# adafruit_rgblcdplate.net
KiCad netlist of a schematic drawn in EAGLE
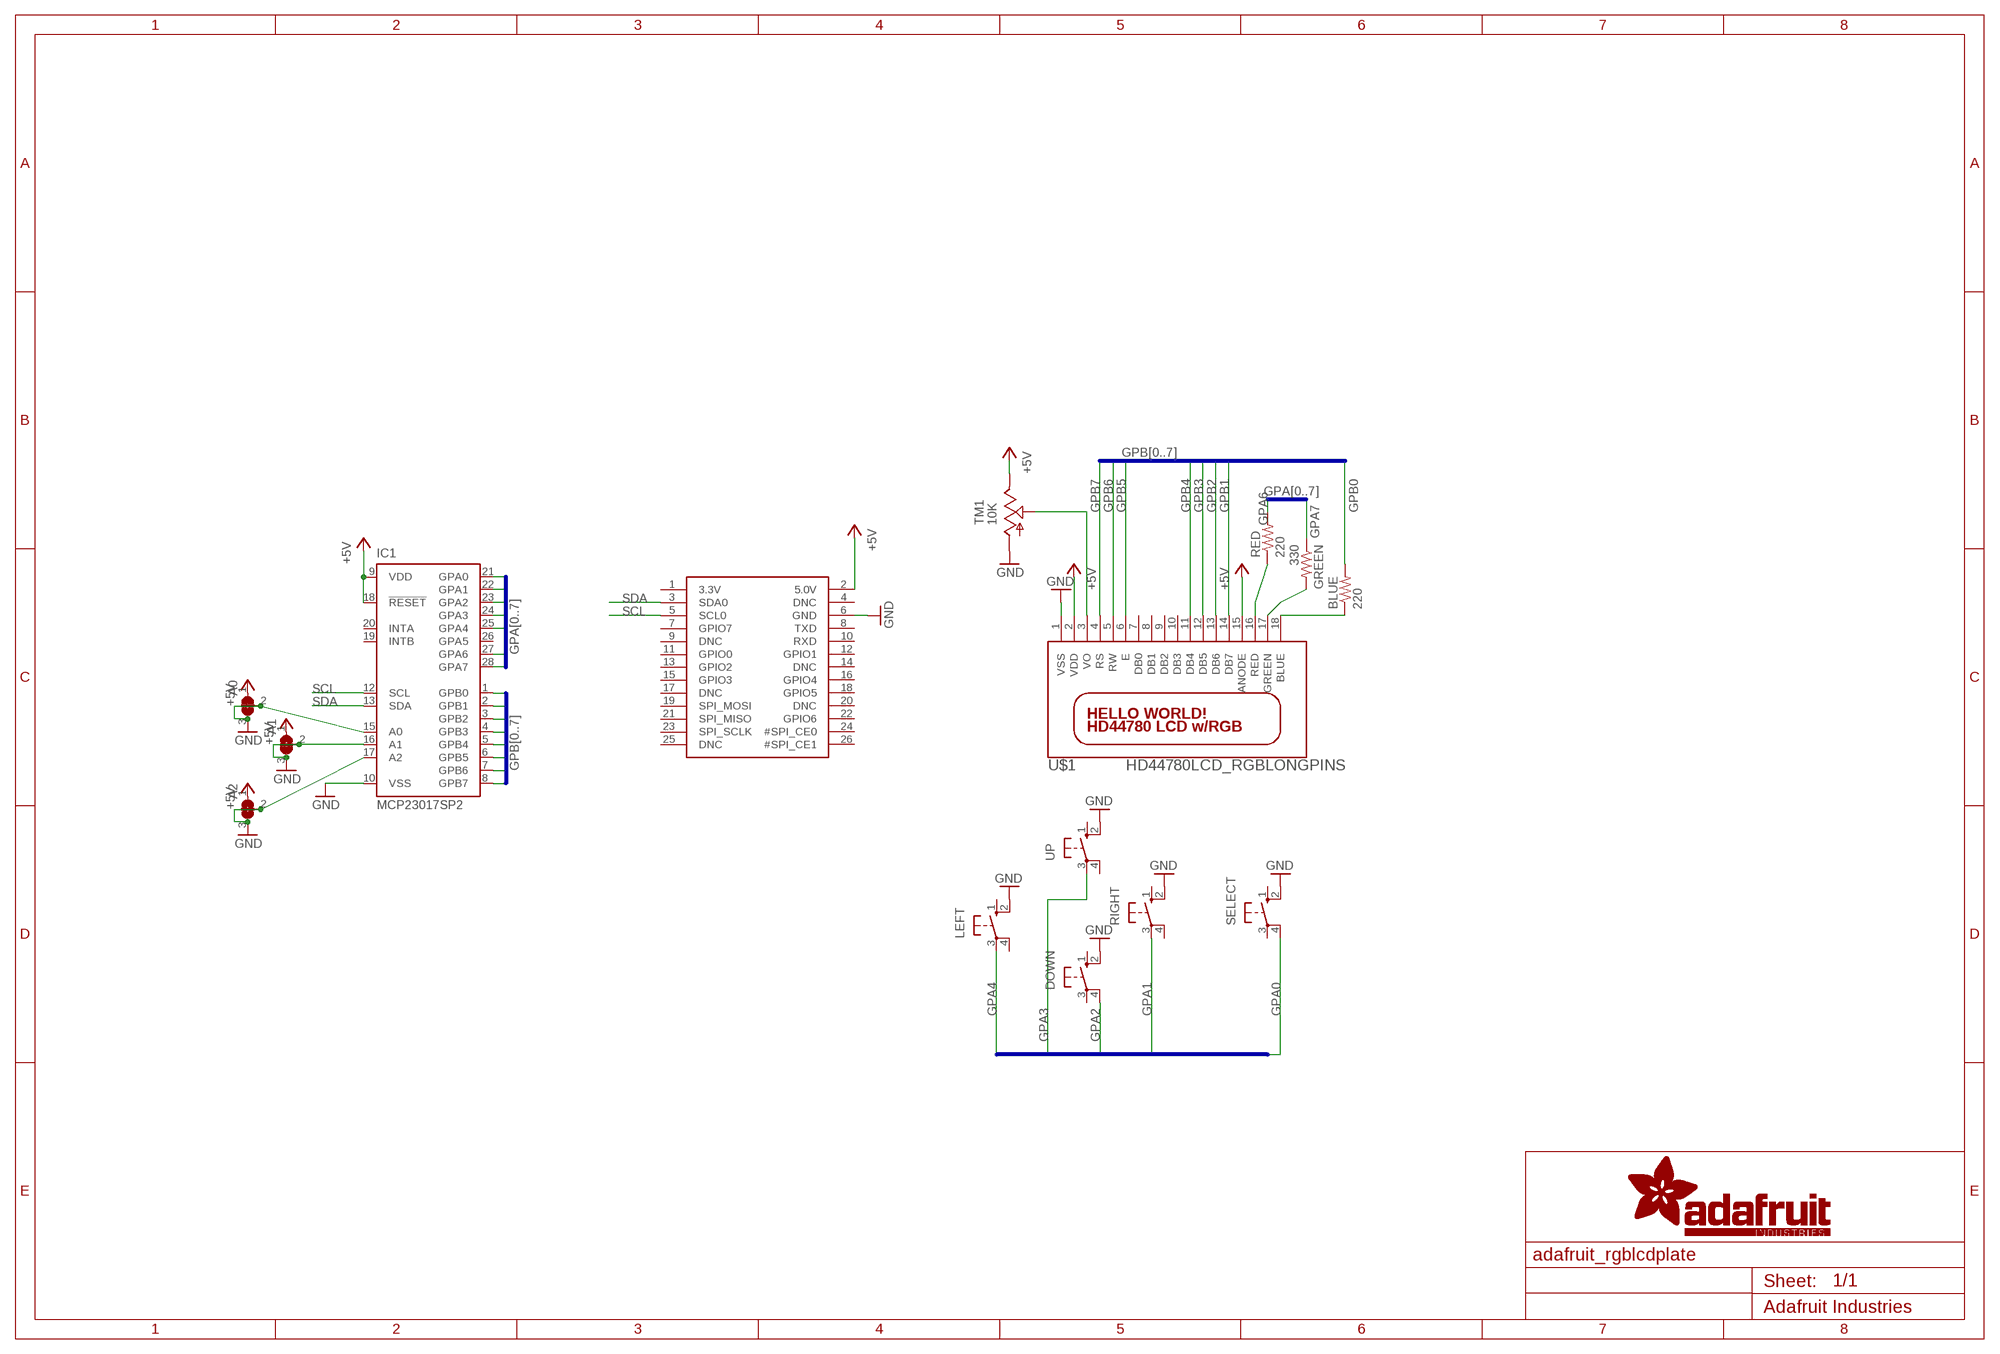
[diagram p0: schematic, sheet 1]

(export (version "E")
  (design (tool "Eeschema 10.0.6"))
  (components
    (comp (ref "A0")
      (value "SOLDERJUMPER_2WAY")
      (footprint "eagle-import:SOLDERJUMPER_2WAY_OPEN_NOPASTE")
      (libsource (lib "eagle-import") (part "SOLDERJUMPER_2WAY"))
    )
    (comp (ref "A1")
      (value "SOLDERJUMPER_2WAY")
      (footprint "eagle-import:SOLDERJUMPER_2WAY_OPEN_NOPASTE")
      (libsource (lib "eagle-import") (part "SOLDERJUMPER_2WAY"))
    )
    (comp (ref "A2")
      (value "SOLDERJUMPER_2WAY")
      (footprint "eagle-import:SOLDERJUMPER_2WAY_OPEN_NOPASTE")
      (libsource (lib "eagle-import") (part "SOLDERJUMPER_2WAY"))
    )
    (comp (ref "BLUE")
      (value "220")
      (footprint "eagle-import:0207_10")
      (libsource (lib "eagle-import") (part "R-US_0207/10"))
    )
    (comp (ref "DOWN")
      (value "10-XX")
      (footprint "eagle-import:B3F-10XX")
      (libsource (lib "eagle-import") (part "10-XX"))
    )
    (comp (ref "GREEN")
      (value "330")
      (footprint "eagle-import:0207_10")
      (libsource (lib "eagle-import") (part "R-US_0207/10"))
    )
    (comp (ref "IC1")
      (value "MCP23017SP2")
      (footprint "eagle-import:DIL28-3-ROUND")
      (libsource (lib "eagle-import") (part "MCP23017SP2"))
    )
    (comp (ref "LEFT")
      (value "10-XX")
      (footprint "eagle-import:B3F-10XX")
      (libsource (lib "eagle-import") (part "10-XX"))
    )
    (comp (ref "RED")
      (value "220")
      (footprint "eagle-import:0207_10")
      (libsource (lib "eagle-import") (part "R-US_0207/10"))
    )
    (comp (ref "RIGHT")
      (value "10-XX")
      (footprint "eagle-import:B3F-10XX")
      (libsource (lib "eagle-import") (part "10-XX"))
    )
    (comp (ref "SELECT")
      (value "10-XX")
      (footprint "eagle-import:B3F-10XX")
      (libsource (lib "eagle-import") (part "10-XX"))
    )
    (comp (ref "TM1")
      (value "10K")
      (footprint "eagle-import:6MM")
      (libsource (lib "eagle-import") (part "TRIM"))
    )
    (comp (ref "U$1")
      (value "HD44780LCD_RGBLONGPINS")
      (footprint "eagle-import:LCD1602-RGB")
      (libsource (lib "eagle-import") (part "HD44780LCD_RGBLONGPINS"))
    )
    (comp (ref "U$4")
      (value "RASPBERRYPI_BB")
      (footprint "eagle-import:RASBERRYPI_SHIELD")
      (libsource (lib "eagle-import") (part "RASPBERRYPI_BB"))
    )
    (comp (ref "UP")
      (value "10-XX")
      (footprint "eagle-import:B3F-10XX")
      (libsource (lib "eagle-import") (part "10-XX"))
    )
  )
  (nets
    (net (code "2") (name "+5V") (class "Default")
      (node (ref "A0") (pin "1") (pinfunction "1_1") (pintype "passive"))
      (node (ref "A1") (pin "1") (pinfunction "1_1") (pintype "passive"))
      (node (ref "A2") (pin "1") (pinfunction "1_1") (pintype "passive"))
      (node (ref "IC1") (pin "18") (pinfunction "~{RESET}_18") (pintype "input"))
      (node (ref "IC1") (pin "9") (pinfunction "VDD_9") (pintype "power_in"))
      (node (ref "TM1") (pin "E") (pinfunction "E_E") (pintype "passive"))
      (node (ref "U$1") (pin "15") (pinfunction "ANODE_15") (pintype "input"))
      (node (ref "U$1") (pin "2") (pinfunction "VDD_2") (pintype "power_in"))
      (node (ref "U$4") (pin "2") (pinfunction "5.0V_2") (pintype "power_in"))
    )
    (net (code "3") (name "/3.3V") (class "Default")
      (node (ref "U$4") (pin "1") (pinfunction "3.3V_1") (pintype "power_in"))
    )
    (net (code "4") (name "/GPA0") (class "Default")
      (node (ref "IC1") (pin "21") (pinfunction "GPA0_21") (pintype "bidirectional"))
      (node (ref "SELECT") (pin "4") (pinfunction "P1_4") (pintype "passive"))
    )
    (net (code "5") (name "/GPA1") (class "Default")
      (node (ref "IC1") (pin "22") (pinfunction "GPA1_22") (pintype "bidirectional"))
      (node (ref "RIGHT") (pin "3") (pinfunction "P_3") (pintype "passive"))
    )
    (net (code "6") (name "/GPA2") (class "Default")
      (node (ref "DOWN") (pin "4") (pinfunction "P1_4") (pintype "passive"))
      (node (ref "IC1") (pin "23") (pinfunction "GPA2_23") (pintype "bidirectional"))
    )
    (net (code "7") (name "/GPA3") (class "Default")
      (node (ref "IC1") (pin "24") (pinfunction "GPA3_24") (pintype "bidirectional"))
      (node (ref "UP") (pin "3") (pinfunction "P_3") (pintype "passive"))
    )
    (net (code "8") (name "/GPA4") (class "Default")
      (node (ref "IC1") (pin "25") (pinfunction "GPA4_25") (pintype "bidirectional"))
      (node (ref "LEFT") (pin "3") (pinfunction "P_3") (pintype "passive"))
    )
    (net (code "9") (name "/GPA6") (class "Default")
      (node (ref "IC1") (pin "27") (pinfunction "GPA6_27") (pintype "bidirectional"))
      (node (ref "RED") (pin "2") (pinfunction "2_2") (pintype "passive"))
    )
    (net (code "10") (name "/GPA7") (class "Default")
      (node (ref "GREEN") (pin "1") (pinfunction "1_1") (pintype "passive"))
      (node (ref "IC1") (pin "28") (pinfunction "GPA7_28") (pintype "bidirectional"))
    )
    (net (code "12") (name "/GPB0") (class "Default")
      (node (ref "BLUE") (pin "2") (pinfunction "2_2") (pintype "passive"))
      (node (ref "IC1") (pin "1") (pinfunction "GPB0_1") (pintype "bidirectional"))
    )
    (net (code "13") (name "/GPB1") (class "Default")
      (node (ref "IC1") (pin "2") (pinfunction "GPB1_2") (pintype "bidirectional"))
      (node (ref "U$1") (pin "14") (pinfunction "DB7_14") (pintype "bidirectional"))
    )
    (net (code "14") (name "/GPB2") (class "Default")
      (node (ref "IC1") (pin "3") (pinfunction "GPB2_3") (pintype "bidirectional"))
      (node (ref "U$1") (pin "13") (pinfunction "DB6_13") (pintype "bidirectional"))
    )
    (net (code "15") (name "/GPB3") (class "Default")
      (node (ref "IC1") (pin "4") (pinfunction "GPB3_4") (pintype "bidirectional"))
      (node (ref "U$1") (pin "12") (pinfunction "DB5_12") (pintype "bidirectional"))
    )
    (net (code "16") (name "/GPB4") (class "Default")
      (node (ref "IC1") (pin "5") (pinfunction "GPB4_5") (pintype "bidirectional"))
      (node (ref "U$1") (pin "11") (pinfunction "DB4_11") (pintype "bidirectional"))
    )
    (net (code "17") (name "/GPB5") (class "Default")
      (node (ref "IC1") (pin "6") (pinfunction "GPB5_6") (pintype "bidirectional"))
      (node (ref "U$1") (pin "6") (pinfunction "E_6") (pintype "input"))
    )
    (net (code "18") (name "/GPB6") (class "Default")
      (node (ref "IC1") (pin "7") (pinfunction "GPB6_7") (pintype "bidirectional"))
      (node (ref "U$1") (pin "5") (pinfunction "RW_5") (pintype "input"))
    )
    (net (code "19") (name "/GPB7") (class "Default")
      (node (ref "IC1") (pin "8") (pinfunction "GPB7_8") (pintype "bidirectional"))
      (node (ref "U$1") (pin "4") (pinfunction "RS_4") (pintype "input"))
    )
    (net (code "21") (name "/SCL") (class "Default")
      (node (ref "IC1") (pin "12") (pinfunction "SCL_12") (pintype "input"))
      (node (ref "U$4") (pin "5") (pinfunction "SCL0_5") (pintype "output"))
    )
    (net (code "22") (name "/SDA") (class "Default")
      (node (ref "IC1") (pin "13") (pinfunction "SDA_13") (pintype "bidirectional"))
      (node (ref "U$4") (pin "3") (pinfunction "SDA0_3") (pintype "bidirectional"))
    )
    (net (code "23") (name "GND") (class "Default")
      (node (ref "A0") (pin "2") (pinfunction "2_2") (pintype "passive"))
      (node (ref "A0") (pin "3") (pinfunction "3_3") (pintype "passive"))
      (node (ref "A1") (pin "2") (pinfunction "2_2") (pintype "passive"))
      (node (ref "A1") (pin "3") (pinfunction "3_3") (pintype "passive"))
      (node (ref "A2") (pin "2") (pinfunction "2_2") (pintype "passive"))
      (node (ref "A2") (pin "3") (pinfunction "3_3") (pintype "passive"))
      (node (ref "DOWN") (pin "2") (pinfunction "S1_2") (pintype "passive"))
      (node (ref "IC1") (pin "10") (pinfunction "VSS_10") (pintype "power_in"))
      (node (ref "IC1") (pin "15") (pinfunction "A0_15") (pintype "input"))
      (node (ref "IC1") (pin "16") (pinfunction "A1_16") (pintype "input"))
      (node (ref "IC1") (pin "17") (pinfunction "A2_17") (pintype "input"))
      (node (ref "LEFT") (pin "2") (pinfunction "S1_2") (pintype "passive"))
      (node (ref "RIGHT") (pin "2") (pinfunction "S1_2") (pintype "passive"))
      (node (ref "SELECT") (pin "2") (pinfunction "S1_2") (pintype "passive"))
      (node (ref "TM1") (pin "A") (pinfunction "A_A") (pintype "passive"))
      (node (ref "U$1") (pin "1") (pinfunction "VSS_1") (pintype "power_in"))
      (node (ref "U$4") (pin "6") (pinfunction "GND_6") (pintype "power_in"))
      (node (ref "UP") (pin "2") (pinfunction "S1_2") (pintype "passive"))
    )
    (net (code "24") (name "Net-(U$1-BLUE)") (class "Default")
      (node (ref "BLUE") (pin "1") (pinfunction "1_1") (pintype "passive"))
      (node (ref "U$1") (pin "18") (pinfunction "BLUE_18") (pintype "input"))
    )
    (net (code "25") (name "Net-(U$1-GREEN)") (class "Default")
      (node (ref "GREEN") (pin "2") (pinfunction "2_2") (pintype "passive"))
      (node (ref "U$1") (pin "17") (pinfunction "GREEN_17") (pintype "input"))
    )
    (net (code "26") (name "Net-(U$1-RED)") (class "Default")
      (node (ref "RED") (pin "1") (pinfunction "1_1") (pintype "passive"))
      (node (ref "U$1") (pin "16") (pinfunction "RED_16") (pintype "input"))
    )
    (net (code "27") (name "Net-(U$1-VO)") (class "Default")
      (node (ref "TM1") (pin "S") (pinfunction "S_S") (pintype "passive"))
      (node (ref "U$1") (pin "3") (pinfunction "VO_3") (pintype "input"))
    )
    (net (code "28") (name "unconnected-(DOWN-P-Pad3)") (class "Default")
      (node (ref "DOWN") (pin "3") (pinfunction "P_3") (pintype "passive"))
    )
    (net (code "29") (name "unconnected-(DOWN-S-Pad1)") (class "Default")
      (node (ref "DOWN") (pin "1") (pinfunction "S_1") (pintype "passive"))
    )
    (net (code "30") (name "unconnected-(IC1-GPA5-Pad26)") (class "Default")
      (node (ref "IC1") (pin "26") (pinfunction "GPA5_26") (pintype "bidirectional"))
    )
    (net (code "31") (name "unconnected-(IC1-INTA-Pad20)") (class "Default")
      (node (ref "IC1") (pin "20") (pinfunction "INTA_20") (pintype "output"))
    )
    (net (code "32") (name "unconnected-(IC1-INTB-Pad19)") (class "Default")
      (node (ref "IC1") (pin "19") (pinfunction "INTB_19") (pintype "output"))
    )
    (net (code "33") (name "unconnected-(LEFT-P1-Pad4)") (class "Default")
      (node (ref "LEFT") (pin "4") (pinfunction "P1_4") (pintype "passive"))
    )
    (net (code "34") (name "unconnected-(LEFT-S-Pad1)") (class "Default")
      (node (ref "LEFT") (pin "1") (pinfunction "S_1") (pintype "passive"))
    )
    (net (code "35") (name "unconnected-(RIGHT-P1-Pad4)") (class "Default")
      (node (ref "RIGHT") (pin "4") (pinfunction "P1_4") (pintype "passive"))
    )
    (net (code "36") (name "unconnected-(RIGHT-S-Pad1)") (class "Default")
      (node (ref "RIGHT") (pin "1") (pinfunction "S_1") (pintype "passive"))
    )
    (net (code "37") (name "unconnected-(SELECT-P-Pad3)") (class "Default")
      (node (ref "SELECT") (pin "3") (pinfunction "P_3") (pintype "passive"))
    )
    (net (code "38") (name "unconnected-(SELECT-S-Pad1)") (class "Default")
      (node (ref "SELECT") (pin "1") (pinfunction "S_1") (pintype "passive"))
    )
    (net (code "39") (name "unconnected-(U$1-DB0-Pad7)") (class "Default")
      (node (ref "U$1") (pin "7") (pinfunction "DB0_7") (pintype "bidirectional"))
    )
    (net (code "40") (name "unconnected-(U$1-DB1-Pad8)") (class "Default")
      (node (ref "U$1") (pin "8") (pinfunction "DB1_8") (pintype "bidirectional"))
    )
    (net (code "41") (name "unconnected-(U$1-DB2-Pad9)") (class "Default")
      (node (ref "U$1") (pin "9") (pinfunction "DB2_9") (pintype "bidirectional"))
    )
    (net (code "42") (name "unconnected-(U$1-DB3-Pad10)") (class "Default")
      (node (ref "U$1") (pin "10") (pinfunction "DB3_10") (pintype "bidirectional"))
    )
    (net (code "43") (name "unconnected-(U$4-#SPI_CE0-Pad24)") (class "Default")
      (node (ref "U$4") (pin "24") (pinfunction "#SPI_CE0_24") (pintype "output"))
    )
    (net (code "44") (name "unconnected-(U$4-#SPI_CE1-Pad26)") (class "Default")
      (node (ref "U$4") (pin "26") (pinfunction "#SPI_CE1_26") (pintype "output"))
    )
    (net (code "45") (name "unconnected-(U$4-DNC-Pad4)") (class "Default")
      (node (ref "U$4") (pin "4") (pinfunction "DNC_4") (pintype "no_connect"))
    )
    (net (code "46") (name "unconnected-(U$4-DNC-Pad9)") (class "Default")
      (node (ref "U$4") (pin "9") (pinfunction "DNC_9") (pintype "no_connect"))
    )
    (net (code "47") (name "unconnected-(U$4-DNC-Pad14)") (class "Default")
      (node (ref "U$4") (pin "14") (pinfunction "DNC_14") (pintype "no_connect"))
    )
    (net (code "48") (name "unconnected-(U$4-DNC-Pad17)") (class "Default")
      (node (ref "U$4") (pin "17") (pinfunction "DNC_17") (pintype "no_connect"))
    )
    (net (code "49") (name "unconnected-(U$4-DNC-Pad20)") (class "Default")
      (node (ref "U$4") (pin "20") (pinfunction "DNC_20") (pintype "no_connect"))
    )
    (net (code "50") (name "unconnected-(U$4-DNC-Pad25)") (class "Default")
      (node (ref "U$4") (pin "25") (pinfunction "DNC_25") (pintype "no_connect"))
    )
    (net (code "51") (name "unconnected-(U$4-GPIO0-Pad11)") (class "Default")
      (node (ref "U$4") (pin "11") (pinfunction "GPIO0_11") (pintype "bidirectional"))
    )
    (net (code "52") (name "unconnected-(U$4-GPIO1-Pad12)") (class "Default")
      (node (ref "U$4") (pin "12") (pinfunction "GPIO1_12") (pintype "bidirectional"))
    )
    (net (code "53") (name "unconnected-(U$4-GPIO2-Pad13)") (class "Default")
      (node (ref "U$4") (pin "13") (pinfunction "GPIO2_13") (pintype "bidirectional"))
    )
    (net (code "54") (name "unconnected-(U$4-GPIO3-Pad15)") (class "Default")
      (node (ref "U$4") (pin "15") (pinfunction "GPIO3_15") (pintype "bidirectional"))
    )
    (net (code "55") (name "unconnected-(U$4-GPIO4-Pad16)") (class "Default")
      (node (ref "U$4") (pin "16") (pinfunction "GPIO4_16") (pintype "bidirectional"))
    )
    (net (code "56") (name "unconnected-(U$4-GPIO5-Pad18)") (class "Default")
      (node (ref "U$4") (pin "18") (pinfunction "GPIO5_18") (pintype "bidirectional"))
    )
    (net (code "57") (name "unconnected-(U$4-GPIO6-Pad22)") (class "Default")
      (node (ref "U$4") (pin "22") (pinfunction "GPIO6_22") (pintype "bidirectional"))
    )
    (net (code "58") (name "unconnected-(U$4-GPIO7-Pad7)") (class "Default")
      (node (ref "U$4") (pin "7") (pinfunction "GPIO7_7") (pintype "bidirectional"))
    )
    (net (code "59") (name "unconnected-(U$4-RXD-Pad10)") (class "Default")
      (node (ref "U$4") (pin "10") (pinfunction "RXD_10") (pintype "input"))
    )
    (net (code "60") (name "unconnected-(U$4-SPI_MISO-Pad21)") (class "Default")
      (node (ref "U$4") (pin "21") (pinfunction "SPI_MISO_21") (pintype "input"))
    )
    (net (code "61") (name "unconnected-(U$4-SPI_MOSI-Pad19)") (class "Default")
      (node (ref "U$4") (pin "19") (pinfunction "SPI_MOSI_19") (pintype "output"))
    )
    (net (code "62") (name "unconnected-(U$4-SPI_SCLK-Pad23)") (class "Default")
      (node (ref "U$4") (pin "23") (pinfunction "SPI_SCLK_23") (pintype "output"))
    )
    (net (code "63") (name "unconnected-(U$4-TXD-Pad8)") (class "Default")
      (node (ref "U$4") (pin "8") (pinfunction "TXD_8") (pintype "output"))
    )
    (net (code "64") (name "unconnected-(UP-P1-Pad4)") (class "Default")
      (node (ref "UP") (pin "4") (pinfunction "P1_4") (pintype "passive"))
    )
    (net (code "65") (name "unconnected-(UP-S-Pad1)") (class "Default")
      (node (ref "UP") (pin "1") (pinfunction "S_1") (pintype "passive"))
    )
  )
)
